# config-bank1.net
KiCad netlist of a schematic drawn in Altium Designer
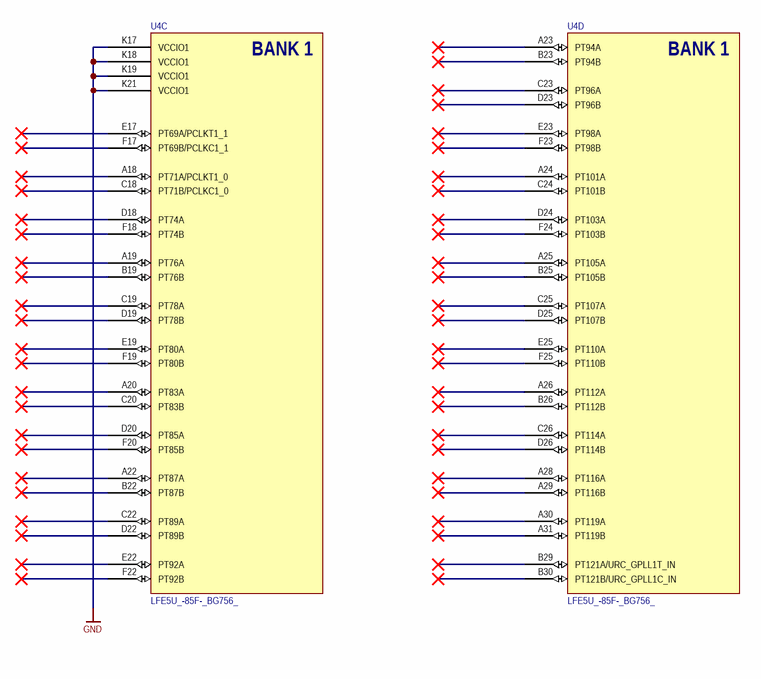
[diagram p0: config-bank1.SchDoc]

(export (version "E")
  (design (tool "Eeschema 10.0.6"))
  (components
    (comp (ref "U4")
      (value "LFE5U_-85F-_BG756_")
      (footprint "lattice:caBGA756")
      (description "ECP5 FPGA, 85k LUT, 756-caBGA")
      (fields (field (name "MANUFACTURER") "Lattice Semiconductor"))
      (libsource (lib "lattice") (part "LFE5U_-85F-_BG756_"))
    )
  )
  (nets
    (net (code "1") (name "GND") (class "Default")
      (node (ref "U4") (pin "K17") (pinfunction "VCCIO1_K17") (pintype "power_in"))
      (node (ref "U4") (pin "K18") (pinfunction "VCCIO1_K18") (pintype "power_in"))
      (node (ref "U4") (pin "K19") (pinfunction "VCCIO1_K19") (pintype "power_in"))
      (node (ref "U4") (pin "K21") (pinfunction "VCCIO1_K21") (pintype "power_in"))
    )
    (net (code "2") (name "unconnected-(U4C-PT69A{slash}PCLKT1_1-PadE17)") (class "Default")
      (node (ref "U4") (pin "E17") (pinfunction "PT69A/PCLKT1_1_E17") (pintype "bidirectional+no_connect"))
    )
    (net (code "3") (name "unconnected-(U4C-PT69B{slash}PCLKC1_1-PadF17)") (class "Default")
      (node (ref "U4") (pin "F17") (pinfunction "PT69B/PCLKC1_1_F17") (pintype "bidirectional+no_connect"))
    )
    (net (code "4") (name "unconnected-(U4C-PT71A{slash}PCLKT1_0-PadA18)") (class "Default")
      (node (ref "U4") (pin "A18") (pinfunction "PT71A/PCLKT1_0_A18") (pintype "bidirectional+no_connect"))
    )
    (net (code "5") (name "unconnected-(U4C-PT71B{slash}PCLKC1_0-PadC18)") (class "Default")
      (node (ref "U4") (pin "C18") (pinfunction "PT71B/PCLKC1_0_C18") (pintype "bidirectional+no_connect"))
    )
    (net (code "6") (name "unconnected-(U4C-PT74A-PadD18)") (class "Default")
      (node (ref "U4") (pin "D18") (pinfunction "PT74A_D18") (pintype "bidirectional+no_connect"))
    )
    (net (code "7") (name "unconnected-(U4C-PT74B-PadF18)") (class "Default")
      (node (ref "U4") (pin "F18") (pinfunction "PT74B_F18") (pintype "bidirectional+no_connect"))
    )
    (net (code "8") (name "unconnected-(U4C-PT76A-PadA19)") (class "Default")
      (node (ref "U4") (pin "A19") (pinfunction "PT76A_A19") (pintype "bidirectional+no_connect"))
    )
    (net (code "9") (name "unconnected-(U4C-PT76B-PadB19)") (class "Default")
      (node (ref "U4") (pin "B19") (pinfunction "PT76B_B19") (pintype "bidirectional+no_connect"))
    )
    (net (code "10") (name "unconnected-(U4C-PT78A-PadC19)") (class "Default")
      (node (ref "U4") (pin "C19") (pinfunction "PT78A_C19") (pintype "bidirectional+no_connect"))
    )
    (net (code "11") (name "unconnected-(U4C-PT78B-PadD19)") (class "Default")
      (node (ref "U4") (pin "D19") (pinfunction "PT78B_D19") (pintype "bidirectional+no_connect"))
    )
    (net (code "12") (name "unconnected-(U4C-PT80A-PadE19)") (class "Default")
      (node (ref "U4") (pin "E19") (pinfunction "PT80A_E19") (pintype "bidirectional+no_connect"))
    )
    (net (code "13") (name "unconnected-(U4C-PT80B-PadF19)") (class "Default")
      (node (ref "U4") (pin "F19") (pinfunction "PT80B_F19") (pintype "bidirectional+no_connect"))
    )
    (net (code "14") (name "unconnected-(U4C-PT83A-PadA20)") (class "Default")
      (node (ref "U4") (pin "A20") (pinfunction "PT83A_A20") (pintype "bidirectional+no_connect"))
    )
    (net (code "15") (name "unconnected-(U4C-PT83B-PadC20)") (class "Default")
      (node (ref "U4") (pin "C20") (pinfunction "PT83B_C20") (pintype "bidirectional+no_connect"))
    )
    (net (code "16") (name "unconnected-(U4C-PT85A-PadD20)") (class "Default")
      (node (ref "U4") (pin "D20") (pinfunction "PT85A_D20") (pintype "bidirectional+no_connect"))
    )
    (net (code "17") (name "unconnected-(U4C-PT85B-PadF20)") (class "Default")
      (node (ref "U4") (pin "F20") (pinfunction "PT85B_F20") (pintype "bidirectional+no_connect"))
    )
    (net (code "18") (name "unconnected-(U4C-PT87A-PadA22)") (class "Default")
      (node (ref "U4") (pin "A22") (pinfunction "PT87A_A22") (pintype "bidirectional+no_connect"))
    )
    (net (code "19") (name "unconnected-(U4C-PT87B-PadB22)") (class "Default")
      (node (ref "U4") (pin "B22") (pinfunction "PT87B_B22") (pintype "bidirectional+no_connect"))
    )
    (net (code "20") (name "unconnected-(U4C-PT89A-PadC22)") (class "Default")
      (node (ref "U4") (pin "C22") (pinfunction "PT89A_C22") (pintype "bidirectional+no_connect"))
    )
    (net (code "21") (name "unconnected-(U4C-PT89B-PadD22)") (class "Default")
      (node (ref "U4") (pin "D22") (pinfunction "PT89B_D22") (pintype "bidirectional+no_connect"))
    )
    (net (code "22") (name "unconnected-(U4C-PT92A-PadE22)") (class "Default")
      (node (ref "U4") (pin "E22") (pinfunction "PT92A_E22") (pintype "bidirectional+no_connect"))
    )
    (net (code "23") (name "unconnected-(U4C-PT92B-PadF22)") (class "Default")
      (node (ref "U4") (pin "F22") (pinfunction "PT92B_F22") (pintype "bidirectional+no_connect"))
    )
    (net (code "24") (name "unconnected-(U4D-PT94A-PadA23)") (class "Default")
      (node (ref "U4") (pin "A23") (pinfunction "PT94A_A23") (pintype "bidirectional+no_connect"))
    )
    (net (code "25") (name "unconnected-(U4D-PT94B-PadB23)") (class "Default")
      (node (ref "U4") (pin "B23") (pinfunction "PT94B_B23") (pintype "bidirectional+no_connect"))
    )
    (net (code "26") (name "unconnected-(U4D-PT96A-PadC23)") (class "Default")
      (node (ref "U4") (pin "C23") (pinfunction "PT96A_C23") (pintype "bidirectional+no_connect"))
    )
    (net (code "27") (name "unconnected-(U4D-PT96B-PadD23)") (class "Default")
      (node (ref "U4") (pin "D23") (pinfunction "PT96B_D23") (pintype "bidirectional+no_connect"))
    )
    (net (code "28") (name "unconnected-(U4D-PT98A-PadE23)") (class "Default")
      (node (ref "U4") (pin "E23") (pinfunction "PT98A_E23") (pintype "bidirectional+no_connect"))
    )
    (net (code "29") (name "unconnected-(U4D-PT98B-PadF23)") (class "Default")
      (node (ref "U4") (pin "F23") (pinfunction "PT98B_F23") (pintype "bidirectional+no_connect"))
    )
    (net (code "30") (name "unconnected-(U4D-PT101A-PadA24)") (class "Default")
      (node (ref "U4") (pin "A24") (pinfunction "PT101A_A24") (pintype "bidirectional+no_connect"))
    )
    (net (code "31") (name "unconnected-(U4D-PT101B-PadC24)") (class "Default")
      (node (ref "U4") (pin "C24") (pinfunction "PT101B_C24") (pintype "bidirectional+no_connect"))
    )
    (net (code "32") (name "unconnected-(U4D-PT103A-PadD24)") (class "Default")
      (node (ref "U4") (pin "D24") (pinfunction "PT103A_D24") (pintype "bidirectional+no_connect"))
    )
    (net (code "33") (name "unconnected-(U4D-PT103B-PadF24)") (class "Default")
      (node (ref "U4") (pin "F24") (pinfunction "PT103B_F24") (pintype "bidirectional+no_connect"))
    )
    (net (code "34") (name "unconnected-(U4D-PT105A-PadA25)") (class "Default")
      (node (ref "U4") (pin "A25") (pinfunction "PT105A_A25") (pintype "bidirectional+no_connect"))
    )
    (net (code "35") (name "unconnected-(U4D-PT105B-PadB25)") (class "Default")
      (node (ref "U4") (pin "B25") (pinfunction "PT105B_B25") (pintype "bidirectional+no_connect"))
    )
    (net (code "36") (name "unconnected-(U4D-PT107A-PadC25)") (class "Default")
      (node (ref "U4") (pin "C25") (pinfunction "PT107A_C25") (pintype "bidirectional+no_connect"))
    )
    (net (code "37") (name "unconnected-(U4D-PT107B-PadD25)") (class "Default")
      (node (ref "U4") (pin "D25") (pinfunction "PT107B_D25") (pintype "bidirectional+no_connect"))
    )
    (net (code "38") (name "unconnected-(U4D-PT110A-PadE25)") (class "Default")
      (node (ref "U4") (pin "E25") (pinfunction "PT110A_E25") (pintype "bidirectional+no_connect"))
    )
    (net (code "39") (name "unconnected-(U4D-PT110B-PadF25)") (class "Default")
      (node (ref "U4") (pin "F25") (pinfunction "PT110B_F25") (pintype "bidirectional+no_connect"))
    )
    (net (code "40") (name "unconnected-(U4D-PT112A-PadA26)") (class "Default")
      (node (ref "U4") (pin "A26") (pinfunction "PT112A_A26") (pintype "bidirectional+no_connect"))
    )
    (net (code "41") (name "unconnected-(U4D-PT112B-PadB26)") (class "Default")
      (node (ref "U4") (pin "B26") (pinfunction "PT112B_B26") (pintype "bidirectional+no_connect"))
    )
    (net (code "42") (name "unconnected-(U4D-PT114A-PadC26)") (class "Default")
      (node (ref "U4") (pin "C26") (pinfunction "PT114A_C26") (pintype "bidirectional+no_connect"))
    )
    (net (code "43") (name "unconnected-(U4D-PT114B-PadD26)") (class "Default")
      (node (ref "U4") (pin "D26") (pinfunction "PT114B_D26") (pintype "bidirectional+no_connect"))
    )
    (net (code "44") (name "unconnected-(U4D-PT116A-PadA28)") (class "Default")
      (node (ref "U4") (pin "A28") (pinfunction "PT116A_A28") (pintype "bidirectional+no_connect"))
    )
    (net (code "45") (name "unconnected-(U4D-PT116B-PadA29)") (class "Default")
      (node (ref "U4") (pin "A29") (pinfunction "PT116B_A29") (pintype "bidirectional+no_connect"))
    )
    (net (code "46") (name "unconnected-(U4D-PT119A-PadA30)") (class "Default")
      (node (ref "U4") (pin "A30") (pinfunction "PT119A_A30") (pintype "bidirectional+no_connect"))
    )
    (net (code "47") (name "unconnected-(U4D-PT119B-PadA31)") (class "Default")
      (node (ref "U4") (pin "A31") (pinfunction "PT119B_A31") (pintype "bidirectional+no_connect"))
    )
    (net (code "48") (name "unconnected-(U4D-PT121A{slash}URC_GPLL1T_IN-PadB29)") (class "Default")
      (node (ref "U4") (pin "B29") (pinfunction "PT121A/URC_GPLL1T_IN_B29") (pintype "bidirectional+no_connect"))
    )
    (net (code "49") (name "unconnected-(U4D-PT121B{slash}URC_GPLL1C_IN-PadB30)") (class "Default")
      (node (ref "U4") (pin "B30") (pinfunction "PT121B/URC_GPLL1C_IN_B30") (pintype "bidirectional+no_connect"))
    )
  )
)
